# power_unit.net
KiCad netlist of a schematic drawn in Altium Designer
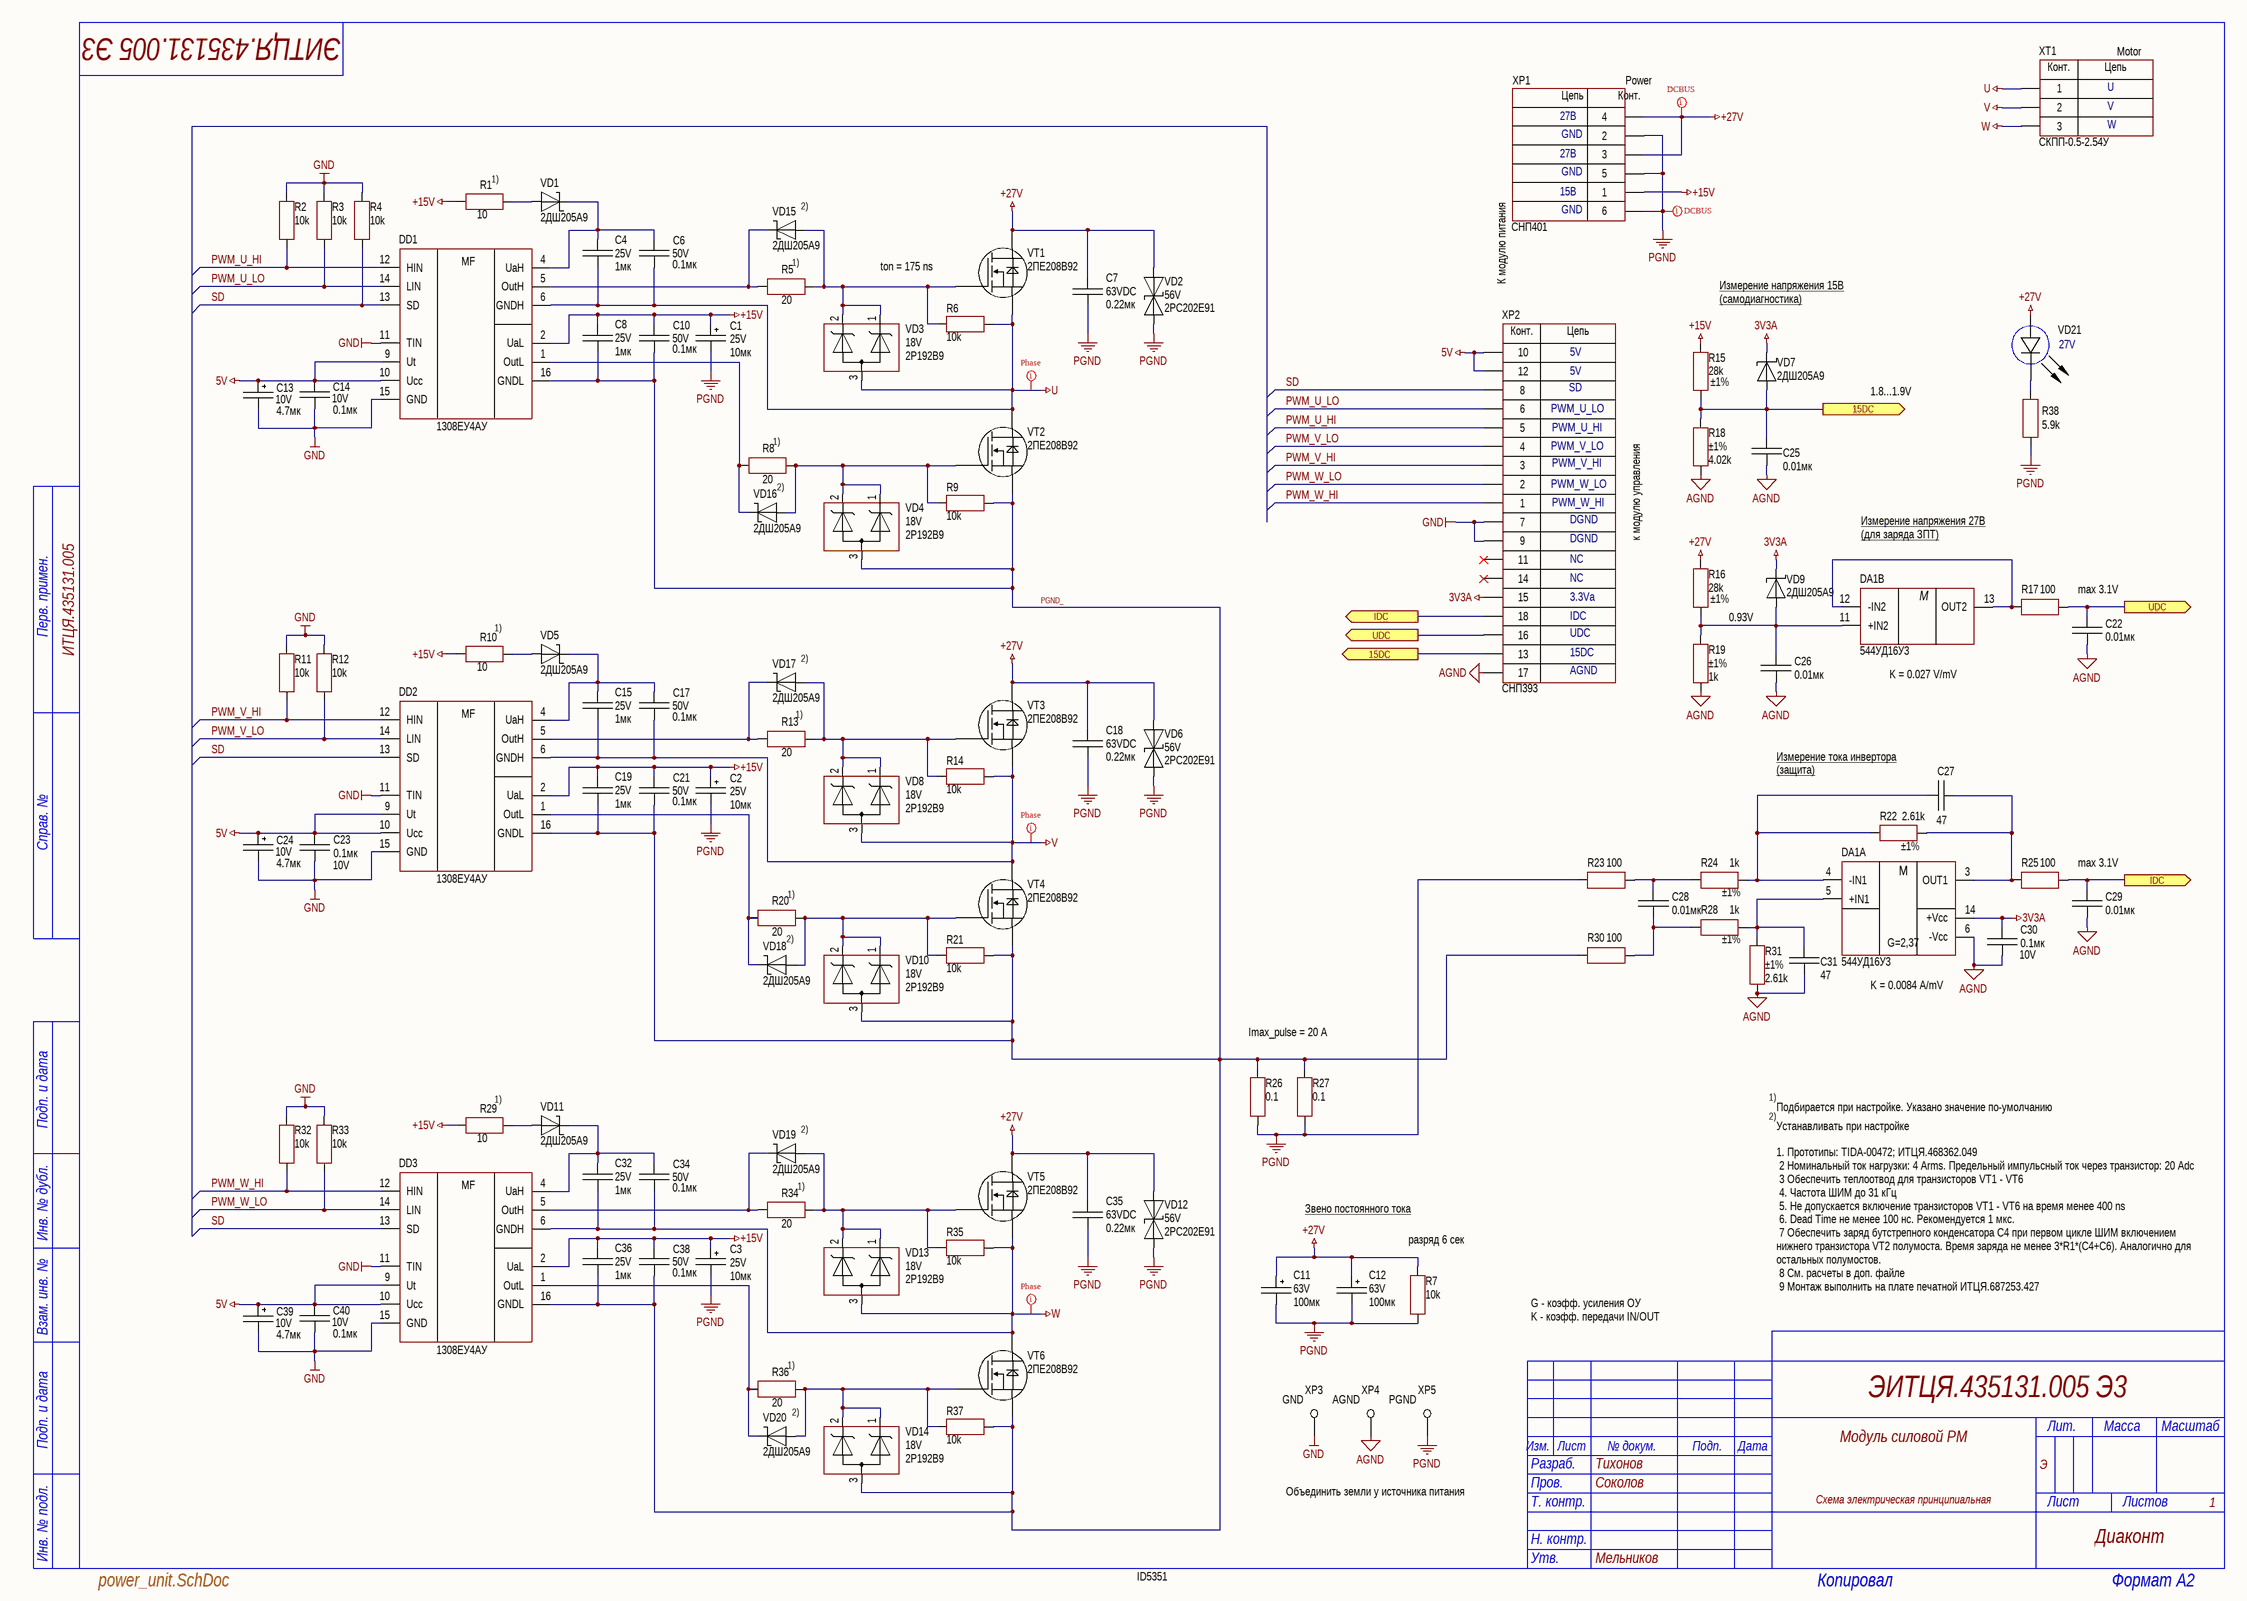
[diagram p0: power_unit.SchDoc]

(export (version "E")
  (design (tool "Eeschema 10.0.6"))
  (components
    (comp (ref "C1")
      (value "10мк")
      (footprint "StandardCase:CAP: TANTAL-C")
      (fields
        (field (name "MANUFACTURER") "Элеконд")
        (field (name "PARTNUMBER") "К53-68 \"С\"-25 В-10 мкф ±10%")
        (field (name "VALUEMANUFACTURERPARTNUMBER") "Tantalum capacitor, 10мк, 25V, ±10%, 0.8-1Ohm, case C (6032), -60...+125°C")
        (field (name "VOLTAGE") "25V")
      )
      (libsource (lib "Capacitor") (part "Tantal_C"))
    )
    (comp (ref "C2")
      (value "10мк")
      (footprint "StandardCase:CAP: TANTAL-C")
      (fields
        (field (name "MANUFACTURER") "Элеконд")
        (field (name "PARTNUMBER") "К53-68 \"С\"-25 В-10 мкф ±10%")
        (field (name "VALUEMANUFACTURERPARTNUMBER") "Tantalum capacitor, 10мк, 25V, ±10%, 0.8-1Ohm, case C (6032), -60...+125°C")
        (field (name "VOLTAGE") "25V")
      )
      (libsource (lib "Capacitor") (part "Tantal_C"))
    )
    (comp (ref "C3")
      (value "10мк")
      (footprint "StandardCase:CAP: TANTAL-C")
      (fields
        (field (name "MANUFACTURER") "Элеконд")
        (field (name "PARTNUMBER") "К53-68 \"С\"-25 В-10 мкф ±10%")
        (field (name "VALUEMANUFACTURERPARTNUMBER") "Tantalum capacitor, 10мк, 25V, ±10%, 0.8-1Ohm, case C (6032), -60...+125°C")
        (field (name "VOLTAGE") "25V")
      )
      (libsource (lib "Capacitor") (part "Tantal_C"))
    )
    (comp (ref "C4")
      (value "1мк")
      (footprint "StandardCase:CAP: 1210")
      (fields
        (field (name "MANUFACTURER") "Monolit")
        (field (name "PARTNUMBER") "К10-84в-3225М-25~В-Н20-1 мкФ-O-A ±10% ФЦТА.673516.016 ТУ")
        (field (name "VALUEMANUFACTURERPARTNUMBER") "Ceramic capacitor, 1мк, Н20 (X7R), ±10%, 25V, 1210, -55...+125°C")
        (field (name "VOLTAGE") "25V")
      )
      (libsource (lib "Capacitor") (part "Ceramic_1210"))
    )
    (comp (ref "C6")
      (value "0.1мк")
      (footprint "StandardCase:CAP: 0805P")
      (fields
        (field (name "MANUFACTURER") "Монолит")
        (field (name "PARTNUMBER") "К10-84в-2012М-50В-0,1 мкФ +80/-20%-Н90-N-A")
        (field (name "VALUEMANUFACTURERPARTNUMBER") "Ceramic capacitor, 0.1мк, Н90 (Y5V), +80 -20%, 50V, 0805 (2012), -55...+125°C")
        (field (name "VOLTAGE") "50V")
      )
      (libsource (lib "Capacitor") (part "Ceramic_0805"))
    )
    (comp (ref "C7")
      (value "0.22мк")
      (footprint "CAP: K73-17 12x10x6")
      (fields
        (field (name "MANUFACTURER") "Гириконд")
        (field (name "PARTNUMBER") "K73-17-63В-0,22мкФ±10%-В АЖЯР.673633.004 ТУ")
        (field (name "VALUEMANUFACTURERPARTNUMBER") "Film capacitor, 0.22мк, 63VDC, ±10%, , 12x10 mm, -60...+125°C")
        (field (name "VOLTAGE") "63VDC")
      )
      (libsource (lib "Capacitor") (part "Film"))
    )
    (comp (ref "C8")
      (value "1мк")
      (footprint "StandardCase:CAP: 1210")
      (fields
        (field (name "MANUFACTURER") "Monolit")
        (field (name "PARTNUMBER") "К10-84в-3225М-25~В-Н20-1 мкФ-O-A ±10% ФЦТА.673516.016 ТУ")
        (field (name "VALUEMANUFACTURERPARTNUMBER") "Ceramic capacitor, 1мк, Н20 (X7R), ±10%, 25V, 1210, -55...+125°C")
        (field (name "VOLTAGE") "25V")
      )
      (libsource (lib "Capacitor") (part "Ceramic_1210"))
    )
    (comp (ref "C10")
      (value "0.1мк")
      (footprint "StandardCase:CAP: 0805P")
      (fields
        (field (name "MANUFACTURER") "Монолит")
        (field (name "PARTNUMBER") "К10-84в-2012М-50В-0,1 мкФ +80/-20%-Н90-N-A")
        (field (name "VALUEMANUFACTURERPARTNUMBER") "Ceramic capacitor, 0.1мк, Н90 (Y5V), +80 -20%, 50V, 0805 (2012), -55...+125°C")
        (field (name "VOLTAGE") "50V")
      )
      (libsource (lib "Capacitor") (part "Ceramic_0805"))
    )
    (comp (ref "C11")
      (value "100мк")
      (footprint "StandardCase:CAP: D8C3.5H12")
      (fields
        (field (name "MANUFACTURER") "Элеконд")
        (field (name "PARTNUMBER") "K50-93-63В-100мкФ ±20% -И-В АЖЯР.673541.021 ТУ")
        (field (name "VALUEMANUFACTURERPARTNUMBER") "Aluminium capacitor, 100мк, 63V, ±20%, 0.342Ohm@100kHz, 8x11.3x3.5 mm, -60...+100°C")
        (field (name "VOLTAGE") "63V")
      )
      (libsource (lib "Capacitor") (part "Aluminium"))
    )
    (comp (ref "C12")
      (value "100мк")
      (footprint "StandardCase:CAP: D8C3.5H12")
      (fields
        (field (name "MANUFACTURER") "Элеконд")
        (field (name "PARTNUMBER") "K50-93-63В-100мкФ ±20% -И-В АЖЯР.673541.021 ТУ")
        (field (name "VALUEMANUFACTURERPARTNUMBER") "Aluminium capacitor, 100мк, 63V, ±20%, 0.342Ohm@100kHz, 8x11.3x3.5 mm, -60...+100°C")
        (field (name "VOLTAGE") "63V")
      )
      (libsource (lib "Capacitor") (part "Aluminium"))
    )
    (comp (ref "C13")
      (value "4.7мк")
      (footprint "StandardCase:CAP: TANTAL-A")
      (fields
        (field (name "MANUFACTURER") "Элеконд")
        (field (name "PARTNUMBER") "К53-68 \"А\"-10 В-4.7 мкф")
        (field (name "VALUEMANUFACTURERPARTNUMBER") "Tantalum capacitor, 4.7мк, 10V, ±10%, 2Ohm, case A (3216), -55...+125°C")
        (field (name "VOLTAGE") "10V")
      )
      (libsource (lib "Capacitor") (part "Tantal_A"))
    )
    (comp (ref "C14")
      (value "0.1мк")
      (footprint "StandardCase:CAP: 0603P")
      (fields
        (field (name "MANUFACTURER") "Гириконд")
        (field (name "PARTNUMBER") "К10-79-10В-0,1 мкФ +80-20% H90")
        (field (name "VALUEMANUFACTURERPARTNUMBER") "Ceramic capacitor, 0.1мк, H90, +80-20%, 10V, 0603, -55...+125°C")
        (field (name "VOLTAGE") "10V")
      )
      (libsource (lib "Capacitor") (part "Ceramic_0603"))
    )
    (comp (ref "C15")
      (value "1мк")
      (footprint "StandardCase:CAP: 1210")
      (fields
        (field (name "MANUFACTURER") "Monolit")
        (field (name "PARTNUMBER") "К10-84в-3225М-25~В-Н20-1 мкФ-O-A ±10% ФЦТА.673516.016 ТУ")
        (field (name "VALUEMANUFACTURERPARTNUMBER") "Ceramic capacitor, 1мк, Н20 (X7R), ±10%, 25V, 1210, -55...+125°C")
        (field (name "VOLTAGE") "25V")
      )
      (libsource (lib "Capacitor") (part "Ceramic_1210"))
    )
    (comp (ref "C17")
      (value "0.1мк")
      (footprint "StandardCase:CAP: 0805P")
      (fields
        (field (name "MANUFACTURER") "Монолит")
        (field (name "PARTNUMBER") "К10-84в-2012М-50В-0,1 мкФ +80/-20%-Н90-N-A")
        (field (name "VALUEMANUFACTURERPARTNUMBER") "Ceramic capacitor, 0.1мк, Н90 (Y5V), +80 -20%, 50V, 0805 (2012), -55...+125°C")
        (field (name "VOLTAGE") "50V")
      )
      (libsource (lib "Capacitor") (part "Ceramic_0805"))
    )
    (comp (ref "C18")
      (value "0.22мк")
      (footprint "CAP: K73-17 12x10x6")
      (fields
        (field (name "MANUFACTURER") "Гириконд")
        (field (name "PARTNUMBER") "K73-17-63В-0,22мкФ±10%-В АЖЯР.673633.004 ТУ")
        (field (name "VALUEMANUFACTURERPARTNUMBER") "Film capacitor, 0.22мк, 63VDC, ±10%, , 12x10 mm, -60...+125°C")
        (field (name "VOLTAGE") "63VDC")
      )
      (libsource (lib "Capacitor") (part "Film"))
    )
    (comp (ref "C19")
      (value "1мк")
      (footprint "StandardCase:CAP: 1210")
      (fields
        (field (name "MANUFACTURER") "Monolit")
        (field (name "PARTNUMBER") "К10-84в-3225М-25~В-Н20-1 мкФ-O-A ±10% ФЦТА.673516.016 ТУ")
        (field (name "VALUEMANUFACTURERPARTNUMBER") "Ceramic capacitor, 1мк, Н20 (X7R), ±10%, 25V, 1210, -55...+125°C")
        (field (name "VOLTAGE") "25V")
      )
      (libsource (lib "Capacitor") (part "Ceramic_1210"))
    )
    (comp (ref "C21")
      (value "0.1мк")
      (footprint "StandardCase:CAP: 0805P")
      (fields
        (field (name "MANUFACTURER") "Монолит")
        (field (name "PARTNUMBER") "К10-84в-2012М-50В-0,1 мкФ +80/-20%-Н90-N-A")
        (field (name "VALUEMANUFACTURERPARTNUMBER") "Ceramic capacitor, 0.1мк, Н90 (Y5V), +80 -20%, 50V, 0805 (2012), -55...+125°C")
        (field (name "VOLTAGE") "50V")
      )
      (libsource (lib "Capacitor") (part "Ceramic_0805"))
    )
    (comp (ref "C22")
      (value "0.01мк")
      (footprint "StandardCase:CAP: 0603P")
      (fields
        (field (name "MANUFACTURER") "Монолит")
        (field (name "PARTNUMBER") "К10-84в-1608М-50В-0.01мк ±20%-Н20-N-A")
        (field (name "VALUEMANUFACTURERPARTNUMBER") "Ceramic capacitor, 0.01мк, H20, ±20%, 50V, 0603, -55...+125°C")
      )
      (libsource (lib "Capacitor") (part "Ceramic_0603"))
    )
    (comp (ref "C23")
      (value "0.1мк")
      (footprint "StandardCase:CAP: 0603P")
      (fields
        (field (name "MANUFACTURER") "Гириконд")
        (field (name "PARTNUMBER") "К10-79-10В-0,1 мкФ +80-20% H90")
        (field (name "VALUEMANUFACTURERPARTNUMBER") "Ceramic capacitor, 0.1мк, H90, +80-20%, 10V, 0603, -55...+125°C")
        (field (name "VOLTAGE") "10V")
      )
      (libsource (lib "Capacitor") (part "Ceramic_0603"))
    )
    (comp (ref "C24")
      (value "4.7мк")
      (footprint "StandardCase:CAP: TANTAL-A")
      (fields
        (field (name "MANUFACTURER") "Элеконд")
        (field (name "PARTNUMBER") "К53-68 \"А\"-10 В-4.7 мкф")
        (field (name "VALUEMANUFACTURERPARTNUMBER") "Tantalum capacitor, 4.7мк, 10V, ±10%, 2Ohm, case A (3216), -55...+125°C")
        (field (name "VOLTAGE") "10V")
      )
      (libsource (lib "Capacitor") (part "Tantal_A"))
    )
    (comp (ref "C25")
      (value "0.01мк")
      (footprint "StandardCase:CAP: 0603P")
      (fields
        (field (name "MANUFACTURER") "Монолит")
        (field (name "PARTNUMBER") "К10-84в-1608М-50В-0.01мк ±20%-Н20-N-A")
        (field (name "VALUEMANUFACTURERPARTNUMBER") "Ceramic capacitor, 0.01мк, H20, ±20%, 50V, 0603, -55...+125°C")
      )
      (libsource (lib "Capacitor") (part "Ceramic_0603"))
    )
    (comp (ref "C26")
      (value "0.01мк")
      (footprint "StandardCase:CAP: 0603P")
      (fields
        (field (name "MANUFACTURER") "Монолит")
        (field (name "PARTNUMBER") "К10-84в-1608М-50В-0.01мк ±20%-Н20-N-A")
        (field (name "VALUEMANUFACTURERPARTNUMBER") "Ceramic capacitor, 0.01мк, H20, ±20%, 50V, 0603, -55...+125°C")
      )
      (libsource (lib "Capacitor") (part "Ceramic_0603"))
    )
    (comp (ref "C27")
      (value "47")
      (footprint "StandardCase:CAP: 0603P")
      (fields
        (field (name "MANUFACTURER") "Монолит")
        (field (name "PARTNUMBER") "К10-84в-1608М-50В-47 пФ ±10%-МП0-N-A")
        (field (name "VALUEMANUFACTURERPARTNUMBER") "Ceramic capacitor, 47, МП0, ±10%, 50V, 0603, -55...+125°C")
      )
      (libsource (lib "Capacitor") (part "Ceramic_0603"))
    )
    (comp (ref "C28")
      (value "0.01мк")
      (footprint "StandardCase:CAP: 0603P")
      (fields
        (field (name "MANUFACTURER") "Монолит")
        (field (name "PARTNUMBER") "К10-84в-1608М-50В-0.01мк ±20%-Н20-N-A")
        (field (name "VALUEMANUFACTURERPARTNUMBER") "Ceramic capacitor, 0.01мк, H20, ±20%, 50V, 0603, -55...+125°C")
      )
      (libsource (lib "Capacitor") (part "Ceramic_0603"))
    )
    (comp (ref "C29")
      (value "0.01мк")
      (footprint "StandardCase:CAP: 0603P")
      (fields
        (field (name "MANUFACTURER") "Монолит")
        (field (name "PARTNUMBER") "К10-84в-1608М-50В-0.01мк ±20%-Н20-N-A")
        (field (name "VALUEMANUFACTURERPARTNUMBER") "Ceramic capacitor, 0.01мк, H20, ±20%, 50V, 0603, -55...+125°C")
      )
      (libsource (lib "Capacitor") (part "Ceramic_0603"))
    )
    (comp (ref "C30")
      (value "0.1мк")
      (footprint "StandardCase:CAP: 0603P")
      (fields
        (field (name "MANUFACTURER") "Гириконд")
        (field (name "PARTNUMBER") "К10-79-10В-0,1 мкФ +80-20% H90")
        (field (name "VALUEMANUFACTURERPARTNUMBER") "Ceramic capacitor, 0.1мк, H90, +80-20%, 10V, 0603, -55...+125°C")
        (field (name "VOLTAGE") "10V")
      )
      (libsource (lib "Capacitor") (part "Ceramic_0603"))
    )
    (comp (ref "C31")
      (value "47")
      (footprint "StandardCase:CAP: 0603P")
      (fields
        (field (name "MANUFACTURER") "Монолит")
        (field (name "PARTNUMBER") "К10-84в-1608М-50В-47 пФ ±10%-МП0-N-A")
        (field (name "VALUEMANUFACTURERPARTNUMBER") "Ceramic capacitor, 47, МП0, ±10%, 50V, 0603, -55...+125°C")
      )
      (libsource (lib "Capacitor") (part "Ceramic_0603"))
    )
    (comp (ref "C32")
      (value "1мк")
      (footprint "StandardCase:CAP: 1210")
      (fields
        (field (name "MANUFACTURER") "Monolit")
        (field (name "PARTNUMBER") "К10-84в-3225М-25~В-Н20-1 мкФ-O-A ±10% ФЦТА.673516.016 ТУ")
        (field (name "VALUEMANUFACTURERPARTNUMBER") "Ceramic capacitor, 1мк, Н20 (X7R), ±10%, 25V, 1210, -55...+125°C")
        (field (name "VOLTAGE") "25V")
      )
      (libsource (lib "Capacitor") (part "Ceramic_1210"))
    )
    (comp (ref "C34")
      (value "0.1мк")
      (footprint "StandardCase:CAP: 0805P")
      (fields
        (field (name "MANUFACTURER") "Монолит")
        (field (name "PARTNUMBER") "К10-84в-2012М-50В-0,1 мкФ +80/-20%-Н90-N-A")
        (field (name "VALUEMANUFACTURERPARTNUMBER") "Ceramic capacitor, 0.1мк, Н90 (Y5V), +80 -20%, 50V, 0805 (2012), -55...+125°C")
        (field (name "VOLTAGE") "50V")
      )
      (libsource (lib "Capacitor") (part "Ceramic_0805"))
    )
    (comp (ref "C35")
      (value "0.22мк")
      (footprint "CAP: K73-17 12x10x6")
      (fields
        (field (name "MANUFACTURER") "Гириконд")
        (field (name "PARTNUMBER") "K73-17-63В-0,22мкФ±10%-В АЖЯР.673633.004 ТУ")
        (field (name "VALUEMANUFACTURERPARTNUMBER") "Film capacitor, 0.22мк, 63VDC, ±10%, , 12x10 mm, -60...+125°C")
        (field (name "VOLTAGE") "63VDC")
      )
      (libsource (lib "Capacitor") (part "Film"))
    )
    (comp (ref "C36")
      (value "1мк")
      (footprint "StandardCase:CAP: 1210")
      (fields
        (field (name "MANUFACTURER") "Monolit")
        (field (name "PARTNUMBER") "К10-84в-3225М-25~В-Н20-1 мкФ-O-A ±10% ФЦТА.673516.016 ТУ")
        (field (name "VALUEMANUFACTURERPARTNUMBER") "Ceramic capacitor, 1мк, Н20 (X7R), ±10%, 25V, 1210, -55...+125°C")
        (field (name "VOLTAGE") "25V")
      )
      (libsource (lib "Capacitor") (part "Ceramic_1210"))
    )
    (comp (ref "C38")
      (value "0.1мк")
      (footprint "StandardCase:CAP: 0805P")
      (fields
        (field (name "MANUFACTURER") "Монолит")
        (field (name "PARTNUMBER") "К10-84в-2012М-50В-0,1 мкФ +80/-20%-Н90-N-A")
        (field (name "VALUEMANUFACTURERPARTNUMBER") "Ceramic capacitor, 0.1мк, Н90 (Y5V), +80 -20%, 50V, 0805 (2012), -55...+125°C")
        (field (name "VOLTAGE") "50V")
      )
      (libsource (lib "Capacitor") (part "Ceramic_0805"))
    )
    (comp (ref "C39")
      (value "4.7мк")
      (footprint "StandardCase:CAP: TANTAL-A")
      (fields
        (field (name "MANUFACTURER") "Элеконд")
        (field (name "PARTNUMBER") "К53-68 \"А\"-10 В-4.7 мкф")
        (field (name "VALUEMANUFACTURERPARTNUMBER") "Tantalum capacitor, 4.7мк, 10V, ±10%, 2Ohm, case A (3216), -55...+125°C")
        (field (name "VOLTAGE") "10V")
      )
      (libsource (lib "Capacitor") (part "Tantal_A"))
    )
    (comp (ref "C40")
      (value "0.1мк")
      (footprint "StandardCase:CAP: 0603P")
      (fields
        (field (name "MANUFACTURER") "Гириконд")
        (field (name "PARTNUMBER") "К10-79-10В-0,1 мкФ +80-20% H90")
        (field (name "VALUEMANUFACTURERPARTNUMBER") "Ceramic capacitor, 0.1мк, H90, +80-20%, 10V, 0603, -55...+125°C")
        (field (name "VOLTAGE") "10V")
      )
      (libsource (lib "Capacitor") (part "Ceramic_0603"))
    )
    (comp (ref "DA1")
      (value "544УД16У3 (Н04.16-1В) АЕЯР.431130.510 ТУ_разнесенная 1")
      (footprint "16-Н04.16-1B")
      (description "Op. Amp rail-to-rail")
      (fields
        (field (name "MANUFACTURER") "НПП \"Восток\"")
        (field (name "PART_NUMBER") "544УД16У3")
        (field (name "PUBLISHER") "Sokolov")
      )
      (libsource (lib "IC. Amplifier") (part "544УД16У3 (Н04.16-1В) АЕЯР.431130.510 ТУ_разнесенная 1"))
    )
    (comp (ref "DD1")
      (value "~")
      (footprint "16-Н04.16-1B")
      (description "Gate driver")
      (fields
        (field (name "MANUFACTURER") "Кремний Эл")
        (field (name "VALUEMANUFACTURERPARTNUMBER") "Hight&Low side gate driver, , , 2A, supply 4...15V, , Н04.16-2В")
        (field (name "PARTNUMBER") "1308ЕУ4АУ")
      )
      (libsource (lib "IC. Gate driver") (part "1308ЕУ4БУ"))
    )
    (comp (ref "DD2")
      (value "~")
      (footprint "16-Н04.16-1B")
      (description "Gate driver")
      (fields
        (field (name "MANUFACTURER") "Кремний Эл")
        (field (name "VALUEMANUFACTURERPARTNUMBER") "Hight&Low side gate driver, , , 2A, supply 4...15V, , Н04.16-2В")
        (field (name "PARTNUMBER") "1308ЕУ4АУ")
      )
      (libsource (lib "IC. Gate driver") (part "1308ЕУ4БУ"))
    )
    (comp (ref "DD3")
      (value "~")
      (footprint "16-Н04.16-1B")
      (description "Gate driver")
      (fields
        (field (name "MANUFACTURER") "Кремний Эл")
        (field (name "VALUEMANUFACTURERPARTNUMBER") "Hight&Low side gate driver, , , 2A, supply 4...15V, , Н04.16-2В")
        (field (name "PARTNUMBER") "1308ЕУ4АУ")
      )
      (libsource (lib "IC. Gate driver") (part "1308ЕУ4БУ"))
    )
    (comp (ref "R1")
      (value "10")
      (footprint "StandardCase:RES: 0603P")
      (fields
        (field (name "MANUFACTURER") "ОАО Ресурс")
        (field (name "PARTNUMBER") "Р1-12-0,1ум.-10~Ом ±2%-М ШКАБ.434110.002 ТУ")
        (field (name "VALUEMANUFACTURERPARTNUMBER") "Resistor film, 10, ±5%, 0603, 0.1W, -55...+125°C")
      )
      (libsource (lib "Resistor") (part "Resistor_0603"))
    )
    (comp (ref "R2")
      (value "10k")
      (footprint "StandardCase:RES: 0603P")
      (fields
        (field (name "MANUFACTURER") "ОАО Ресурс")
        (field (name "PARTNUMBER") "Р1-12-0,1ум.-10~кОм ±5%-М ШКАБ.434110.002 ТУ")
        (field (name "VALUEMANUFACTURERPARTNUMBER") "Resistor film, 10k, ±5%, 0603, 0.1W, -55...+125°C")
      )
      (libsource (lib "") (part "Resistor_0603_1"))
    )
    (comp (ref "R3")
      (value "10k")
      (footprint "StandardCase:RES: 0603P")
      (fields
        (field (name "MANUFACTURER") "ОАО Ресурс")
        (field (name "PARTNUMBER") "Р1-12-0,1ум.-10~кОм ±5%-М ШКАБ.434110.002 ТУ")
        (field (name "VALUEMANUFACTURERPARTNUMBER") "Resistor film, 10k, ±5%, 0603, 0.1W, -55...+125°C")
      )
      (libsource (lib "") (part "Resistor_0603_1"))
    )
    (comp (ref "R4")
      (value "10k")
      (footprint "StandardCase:RES: 0603P")
      (fields
        (field (name "MANUFACTURER") "ОАО Ресурс")
        (field (name "PARTNUMBER") "Р1-12-0,1ум.-10~кОм ±5%-М ШКАБ.434110.002 ТУ")
        (field (name "VALUEMANUFACTURERPARTNUMBER") "Resistor film, 10k, ±5%, 0603, 0.1W, -55...+125°C")
      )
      (libsource (lib "") (part "Resistor_0603_1"))
    )
    (comp (ref "R5")
      (value "20")
      (footprint "StandardCase:RES: 0805P")
      (fields
        (field (name "MANUFACTURER") "ОАО Ресурс")
        (field (name "PARTNUMBER") "Р1-12-0,125-20 Ом ±1%-М ШКАБ.434110.002 ТУ")
        (field (name "VALUEMANUFACTURERPARTNUMBER") "Resistor film, 20, ±1%, 0805, 0.125W, -55...+125°C")
      )
      (libsource (lib "Resistor") (part "Resistor_0805"))
    )
    (comp (ref "R6")
      (value "10k")
      (footprint "StandardCase:RES: 0603P")
      (fields
        (field (name "MANUFACTURER") "ОАО Ресурс")
        (field (name "PARTNUMBER") "Р1-12-0,1ум.-10~кОм ±5%-М ШКАБ.434110.002 ТУ")
        (field (name "VALUEMANUFACTURERPARTNUMBER") "Resistor film, 10k, ±5%, 0603, 0.1W, -55...+125°C")
      )
      (libsource (lib "") (part "Resistor_0603_2"))
    )
    (comp (ref "R7")
      (value "10k")
      (footprint "RES: 0805P")
      (fields
        (field (name "MANUFACTURER") "ОАО Ресурс")
        (field (name "PARTNUMBER") "Р1-12-0,125-10~кОм ±1%-М ШКАБ.434110.002 ТУ")
        (field (name "VALUEMANUFACTURERPARTNUMBER") "Resistor film, 10k, ±1%, 0805, 0.125W, -55...+125°C")
      )
      (libsource (lib "") (part "Resistor_0603_1"))
    )
    (comp (ref "R8")
      (value "20")
      (footprint "StandardCase:RES: 0805P")
      (fields
        (field (name "MANUFACTURER") "ОАО Ресурс")
        (field (name "PARTNUMBER") "Р1-12-0,125-20 Ом ±1%-М ШКАБ.434110.002 ТУ")
        (field (name "VALUEMANUFACTURERPARTNUMBER") "Resistor film, 20, ±1%, 0805, 0.125W, -55...+125°C")
      )
      (libsource (lib "Resistor") (part "Resistor_0805"))
    )
    (comp (ref "R9")
      (value "10k")
      (footprint "StandardCase:RES: 0603P")
      (fields
        (field (name "MANUFACTURER") "ОАО Ресурс")
        (field (name "PARTNUMBER") "Р1-12-0,1ум.-10~кОм ±5%-М ШКАБ.434110.002 ТУ")
        (field (name "VALUEMANUFACTURERPARTNUMBER") "Resistor film, 10k, ±5%, 0603, 0.1W, -55...+125°C")
      )
      (libsource (lib "") (part "Resistor_0603_2"))
    )
    (comp (ref "R10")
      (value "10")
      (footprint "StandardCase:RES: 0603P")
      (fields
        (field (name "MANUFACTURER") "ОАО Ресурс")
        (field (name "PARTNUMBER") "Р1-12-0,1ум.-10~Ом ±2%-М ШКАБ.434110.002 ТУ")
        (field (name "VALUEMANUFACTURERPARTNUMBER") "Resistor film, 10, ±5%, 0603, 0.1W, -55...+125°C")
      )
      (libsource (lib "Resistor") (part "Resistor_0603"))
    )
    (comp (ref "R11")
      (value "10k")
      (footprint "StandardCase:RES: 0603P")
      (fields
        (field (name "MANUFACTURER") "ОАО Ресурс")
        (field (name "PARTNUMBER") "Р1-12-0,1ум.-10~кОм ±5%-М ШКАБ.434110.002 ТУ")
        (field (name "VALUEMANUFACTURERPARTNUMBER") "Resistor film, 10k, ±5%, 0603, 0.1W, -55...+125°C")
      )
      (libsource (lib "") (part "Resistor_0603_1"))
    )
    (comp (ref "R12")
      (value "10k")
      (footprint "StandardCase:RES: 0603P")
      (fields
        (field (name "MANUFACTURER") "ОАО Ресурс")
        (field (name "PARTNUMBER") "Р1-12-0,1ум.-10~кОм ±5%-М ШКАБ.434110.002 ТУ")
        (field (name "VALUEMANUFACTURERPARTNUMBER") "Resistor film, 10k, ±5%, 0603, 0.1W, -55...+125°C")
      )
      (libsource (lib "") (part "Resistor_0603_1"))
    )
    (comp (ref "R13")
      (value "20")
      (footprint "StandardCase:RES: 0805P")
      (fields
        (field (name "MANUFACTURER") "ОАО Ресурс")
        (field (name "PARTNUMBER") "Р1-12-0,125-20 Ом ±1%-М ШКАБ.434110.002 ТУ")
        (field (name "VALUEMANUFACTURERPARTNUMBER") "Resistor film, 20, ±1%, 0805, 0.125W, -55...+125°C")
      )
      (libsource (lib "Resistor") (part "Resistor_0805"))
    )
    (comp (ref "R14")
      (value "10k")
      (footprint "StandardCase:RES: 0603P")
      (fields
        (field (name "MANUFACTURER") "ОАО Ресурс")
        (field (name "PARTNUMBER") "Р1-12-0,1ум.-10~кОм ±5%-М ШКАБ.434110.002 ТУ")
        (field (name "VALUEMANUFACTURERPARTNUMBER") "Resistor film, 10k, ±5%, 0603, 0.1W, -55...+125°C")
      )
      (libsource (lib "") (part "Resistor_0603_2"))
    )
    (comp (ref "R15")
      (value "28k")
      (footprint "StandardCase:RES: 0603P")
      (fields
        (field (name "MANUFACTURER") "ОАО Ресурс")
        (field (name "PARTNUMBER") "Р1-12-0,1ум.-28~кОм ±5%-М ШКАБ.434110.002 ТУ")
        (field (name "VALUEMANUFACTURERPARTNUMBER") "Resistor film, 28k, ±1%, 0603, 0.1W, -55...+125°C")
        (field (name "TOLERANCE") "±1%")
      )
      (libsource (lib "") (part "Resistor_0603_1"))
    )
    (comp (ref "R16")
      (value "28k")
      (footprint "StandardCase:RES: 0603P")
      (fields
        (field (name "MANUFACTURER") "ОАО Ресурс")
        (field (name "PARTNUMBER") "Р1-12-0,1ум.-28~кОм ±5%-М ШКАБ.434110.002 ТУ")
        (field (name "VALUEMANUFACTURERPARTNUMBER") "Resistor film, 28k, ±1%, 0603, 0.1W, -55...+125°C")
        (field (name "TOLERANCE") "±1%")
      )
      (libsource (lib "") (part "Resistor_0603_1"))
    )
    (comp (ref "R17")
      (value "100")
      (footprint "StandardCase:RES: 0603P")
      (fields
        (field (name "MANUFACTURER") "ОАО Ресурс")
        (field (name "PARTNUMBER") "Р1-12-0,1ум.-100~Ом ±5%-М ШКАБ.434110.002 ТУ")
        (field (name "VALUEMANUFACTURERPARTNUMBER") "Resistor film, 100, ±5%, 0603, 0.1W, -55...+125°C")
      )
      (libsource (lib "Resistor") (part "Resistor_0603"))
    )
    (comp (ref "R18")
      (value "4.02k")
      (footprint "StandardCase:RES: 0603P")
      (fields
        (field (name "MANUFACTURER") "ОАО Ресурс")
        (field (name "PARTNUMBER") "Р1-12-0,1ум.-4.02~кОм±1%-М ШКАБ.434110.002 ТУ")
        (field (name "VALUEMANUFACTURERPARTNUMBER") "Resistor film, 4.02k, ±1%, 0603, 0.1W, -55...+125°C")
        (field (name "TOLERANCE") "±1%")
      )
      (libsource (lib "") (part "Resistor_0603_1"))
    )
    (comp (ref "R19")
      (value "1k")
      (footprint "StandardCase:RES: 0603P")
      (fields
        (field (name "MANUFACTURER") "ОАО Ресурс")
        (field (name "PARTNUMBER") "Р1-12-0,1ум.-1~кОм ±1%-М ШКАБ.434110.002 ТУ")
        (field (name "VALUEMANUFACTURERPARTNUMBER") "Resistor film, 1k, ±1%, 0603, 0.1W, -55...+125°C")
        (field (name "TOLERANCE") "±1%")
      )
      (libsource (lib "") (part "Resistor_0603_1"))
    )
    (comp (ref "R20")
      (value "20")
      (footprint "StandardCase:RES: 0805P")
      (fields
        (field (name "MANUFACTURER") "ОАО Ресурс")
        (field (name "PARTNUMBER") "Р1-12-0,125-20 Ом ±1%-М ШКАБ.434110.002 ТУ")
        (field (name "VALUEMANUFACTURERPARTNUMBER") "Resistor film, 20, ±1%, 0805, 0.125W, -55...+125°C")
      )
      (libsource (lib "Resistor") (part "Resistor_0805"))
    )
    (comp (ref "R21")
      (value "10k")
      (footprint "StandardCase:RES: 0603P")
      (fields
        (field (name "MANUFACTURER") "ОАО Ресурс")
        (field (name "PARTNUMBER") "Р1-12-0,1ум.-10~кОм ±5%-М ШКАБ.434110.002 ТУ")
        (field (name "VALUEMANUFACTURERPARTNUMBER") "Resistor film, 10k, ±5%, 0603, 0.1W, -55...+125°C")
      )
      (libsource (lib "") (part "Resistor_0603_2"))
    )
    (comp (ref "R22")
      (value "2.61k")
      (footprint "StandardCase:RES: 0603P")
      (fields
        (field (name "MANUFACTURER") "ОАО Ресурс")
        (field (name "PARTNUMBER") "Р1-12-0,1ум.-2.61~кОм±1%-М ШКАБ.434110.002 ТУ")
        (field (name "VALUEMANUFACTURERPARTNUMBER") "Resistor film, 2.61k, ±1%, 0603, 0.1W, -55...+125°C")
        (field (name "TOLERANCE") "±1%")
      )
      (libsource (lib "Resistor") (part "Resistor_0603"))
    )
    (comp (ref "R23")
      (value "100")
      (footprint "StandardCase:RES: 0603P")
      (fields
        (field (name "MANUFACTURER") "ОАО Ресурс")
        (field (name "PARTNUMBER") "Р1-12-0,1ум.-100~Ом ±5%-М ШКАБ.434110.002 ТУ")
        (field (name "VALUEMANUFACTURERPARTNUMBER") "Resistor film, 100, ±5%, 0603, 0.1W, -55...+125°C")
      )
      (libsource (lib "Resistor") (part "Resistor_0603"))
    )
    (comp (ref "R24")
      (value "1k")
      (footprint "StandardCase:RES: 0603P")
      (fields
        (field (name "MANUFACTURER") "ОАО Ресурс")
        (field (name "PARTNUMBER") "Р1-12-0,1ум.-1~кОм ±1%-М ШКАБ.434110.002 ТУ")
        (field (name "VALUEMANUFACTURERPARTNUMBER") "Resistor film, 1k, ±1%, 0603, 0.1W, -55...+125°C")
        (field (name "TOLERANCE") "±1%")
      )
      (libsource (lib "Resistor") (part "Resistor_0603"))
    )
    (comp (ref "R25")
      (value "100")
      (footprint "StandardCase:RES: 0603P")
      (fields
        (field (name "MANUFACTURER") "ОАО Ресурс")
        (field (name "PARTNUMBER") "Р1-12-0,1ум.-100~Ом ±5%-М ШКАБ.434110.002 ТУ")
        (field (name "VALUEMANUFACTURERPARTNUMBER") "Resistor film, 100, ±5%, 0603, 0.1W, -55...+125°C")
      )
      (libsource (lib "Resistor") (part "Resistor_0603"))
    )
    (comp (ref "R26")
      (value "0.1")
      (footprint "StandardCase:RES: 2512")
      (fields
        (field (name "MANUFACTURER") "Эркон")
        (field (name "PARTNUMBER") "Р2-105-0,75-0,1 Ом±1% А РМУ.434150.001 ТУ")
        (field (name "VALUEMANUFACTURERPARTNUMBER") "Resistor film, 0.1, ±1%, 2512, 0.75W, -55...+125°C")
      )
      (libsource (lib "Resistor") (part "Resistor_2512"))
    )
    (comp (ref "R27")
      (value "0.1")
      (footprint "StandardCase:RES: 2512")
      (fields
        (field (name "MANUFACTURER") "Эркон")
        (field (name "PARTNUMBER") "Р2-105-0,75-0,1 Ом±1% А РМУ.434150.001 ТУ")
        (field (name "VALUEMANUFACTURERPARTNUMBER") "Resistor film, 0.1, ±1%, 2512, 0.75W, -55...+125°C")
      )
      (libsource (lib "Resistor") (part "Resistor_2512"))
    )
    (comp (ref "R28")
      (value "1k")
      (footprint "StandardCase:RES: 0603P")
      (fields
        (field (name "MANUFACTURER") "ОАО Ресурс")
        (field (name "PARTNUMBER") "Р1-12-0,1ум.-1~кОм ±1%-М ШКАБ.434110.002 ТУ")
        (field (name "VALUEMANUFACTURERPARTNUMBER") "Resistor film, 1k, ±1%, 0603, 0.1W, -55...+125°C")
        (field (name "TOLERANCE") "±1%")
      )
      (libsource (lib "Resistor") (part "Resistor_0603"))
    )
    (comp (ref "R29")
      (value "10")
      (footprint "StandardCase:RES: 0603P")
      (fields
        (field (name "MANUFACTURER") "ОАО Ресурс")
        (field (name "PARTNUMBER") "Р1-12-0,1ум.-10~Ом ±2%-М ШКАБ.434110.002 ТУ")
        (field (name "VALUEMANUFACTURERPARTNUMBER") "Resistor film, 10, ±5%, 0603, 0.1W, -55...+125°C")
      )
      (libsource (lib "Resistor") (part "Resistor_0603"))
    )
    (comp (ref "R30")
      (value "100")
      (footprint "StandardCase:RES: 0603P")
      (fields
        (field (name "MANUFACTURER") "ОАО Ресурс")
        (field (name "PARTNUMBER") "Р1-12-0,1ум.-100~Ом ±5%-М ШКАБ.434110.002 ТУ")
        (field (name "VALUEMANUFACTURERPARTNUMBER") "Resistor film, 100, ±5%, 0603, 0.1W, -55...+125°C")
      )
      (libsource (lib "Resistor") (part "Resistor_0603"))
    )
    (comp (ref "R31")
      (value "2.61k")
      (footprint "StandardCase:RES: 0603P")
      (fields
        (field (name "MANUFACTURER") "ОАО Ресурс")
        (field (name "PARTNUMBER") "Р1-12-0,1ум.-2.61~кОм±1%-М ШКАБ.434110.002 ТУ")
        (field (name "VALUEMANUFACTURERPARTNUMBER") "Resistor film, 2.61k, ±1%, 0603, 0.1W, -55...+125°C")
        (field (name "TOLERANCE") "±1%")
      )
      (libsource (lib "") (part "Resistor_0603_1"))
    )
    (comp (ref "R32")
      (value "10k")
      (footprint "StandardCase:RES: 0603P")
      (fields
        (field (name "MANUFACTURER") "ОАО Ресурс")
        (field (name "PARTNUMBER") "Р1-12-0,1ум.-10~кОм ±5%-М ШКАБ.434110.002 ТУ")
        (field (name "VALUEMANUFACTURERPARTNUMBER") "Resistor film, 10k, ±5%, 0603, 0.1W, -55...+125°C")
      )
      (libsource (lib "") (part "Resistor_0603_1"))
    )
    (comp (ref "R33")
      (value "10k")
      (footprint "StandardCase:RES: 0603P")
      (fields
        (field (name "MANUFACTURER") "ОАО Ресурс")
        (field (name "PARTNUMBER") "Р1-12-0,1ум.-10~кОм ±5%-М ШКАБ.434110.002 ТУ")
        (field (name "VALUEMANUFACTURERPARTNUMBER") "Resistor film, 10k, ±5%, 0603, 0.1W, -55...+125°C")
      )
      (libsource (lib "") (part "Resistor_0603_1"))
    )
    (comp (ref "R34")
      (value "20")
      (footprint "StandardCase:RES: 0805P")
      (fields
        (field (name "MANUFACTURER") "ОАО Ресурс")
        (field (name "PARTNUMBER") "Р1-12-0,125-20 Ом ±1%-М ШКАБ.434110.002 ТУ")
        (field (name "VALUEMANUFACTURERPARTNUMBER") "Resistor film, 20, ±1%, 0805, 0.125W, -55...+125°C")
      )
      (libsource (lib "Resistor") (part "Resistor_0805"))
    )
    (comp (ref "R35")
      (value "10k")
      (footprint "StandardCase:RES: 0603P")
      (fields
        (field (name "MANUFACTURER") "ОАО Ресурс")
        (field (name "PARTNUMBER") "Р1-12-0,1ум.-10~кОм ±5%-М ШКАБ.434110.002 ТУ")
        (field (name "VALUEMANUFACTURERPARTNUMBER") "Resistor film, 10k, ±5%, 0603, 0.1W, -55...+125°C")
      )
      (libsource (lib "") (part "Resistor_0603_2"))
    )
    (comp (ref "R36")
      (value "20")
      (footprint "StandardCase:RES: 0805P")
      (fields
        (field (name "MANUFACTURER") "ОАО Ресурс")
        (field (name "PARTNUMBER") "Р1-12-0,125-20 Ом ±1%-М ШКАБ.434110.002 ТУ")
        (field (name "VALUEMANUFACTURERPARTNUMBER") "Resistor film, 20, ±1%, 0805, 0.125W, -55...+125°C")
      )
      (libsource (lib "Resistor") (part "Resistor_0805"))
    )
    (comp (ref "R37")
      (value "10k")
      (footprint "StandardCase:RES: 0603P")
      (fields
        (field (name "MANUFACTURER") "ОАО Ресурс")
        (field (name "PARTNUMBER") "Р1-12-0,1ум.-10~кОм ±5%-М ШКАБ.434110.002 ТУ")
        (field (name "VALUEMANUFACTURERPARTNUMBER") "Resistor film, 10k, ±5%, 0603, 0.1W, -55...+125°C")
      )
      (libsource (lib "") (part "Resistor_0603_2"))
    )
    (comp (ref "R38")
      (value "5.9k")
      (footprint "RES: 0805P")
      (fields
        (field (name "MANUFACTURER") "ОАО Ресурс")
        (field (name "PARTNUMBER") "Р1-12-0,1-5.9~кОм ±5%-М ШКАБ.434110.002 ТУ")
        (field (name "VALUEMANUFACTURERPARTNUMBER") "Resistor film, 5.9k, ±5%, 0805, 0.1W, -55...+125°C")
      )
      (libsource (lib "Resistor") (part "Resistor_0603"))
    )
    (comp (ref "VD1")
      (value "~")
      (footprint "SOT23")
      (fields
        (field (name "MANUFACTURER") "ВЗПП Воронеж")
        (field (name "VALUEMANUFACTURERPARTNUMBER") "shottki diode, 80V, 500mA; max 5 A@1ms, 0.8V, <22ns, SOT-23, -55...+150°C")
        (field (name "VOLTAGE") "80V")
        (field (name "PARTNUMBER") "2ДШ205А9")
      )
      (libsource (lib "Power_unit-RM") (part "2ДШ205А9_SOT-23"))
    )
    (comp (ref "VD2")
      (value "~")
      (footprint "StandardCase:DIODE: SMB")
      (fields
        (field (name "MANUFACTURER") "ВЗПП")
        (field (name "VALUEMANUFACTURERPARTNUMBER") "Zener diode, 56V, 8A, 0.9V, , SMB, -55...+150°C")
        (field (name "VOLTAGE") "56V")
        (field (name "PARTNUMBER") "2РС202Е91")
      )
      (libsource (lib "Diode") (part "TVS_single"))
    )
    (comp (ref "VD3")
      (value "~")
      (footprint "StandardCase:SOT23")
      (fields
        (field (name "MANUFACTURER") "КРИП")
        (field (name "VALUEMANUFACTURERPARTNUMBER") "TVS diode, 18V, 1A, , , SOT-23, -55...+150°C")
        (field (name "VOLTAGE") "18V")
        (field (name "PARTNUMBER") "2Р192В9")
      )
      (libsource (lib "Diode") (part "TVS_array_var2"))
    )
    (comp (ref "VD4")
      (value "~")
      (footprint "StandardCase:SOT23")
      (fields
        (field (name "MANUFACTURER") "КРИП")
        (field (name "VALUEMANUFACTURERPARTNUMBER") "TVS diode, 18V, 1A, , , SOT-23, -55...+150°C")
        (field (name "VOLTAGE") "18V")
        (field (name "PARTNUMBER") "2Р192В9")
      )
      (libsource (lib "Diode") (part "TVS_array_var2"))
    )
    (comp (ref "VD5")
      (value "~")
      (footprint "SOT23")
      (fields
        (field (name "MANUFACTURER") "ВЗПП Воронеж")
        (field (name "VALUEMANUFACTURERPARTNUMBER") "shottki diode, 80V, 500mA; max 5 A@1ms, 0.8V, <22ns, SOT-23, -55...+150°C")
        (field (name "VOLTAGE") "80V")
        (field (name "PARTNUMBER") "2ДШ205А9")
      )
      (libsource (lib "Power_unit-RM") (part "2ДШ205А9_SOT-23"))
    )
    (comp (ref "VD6")
      (value "~")
      (footprint "StandardCase:DIODE: SMB")
      (fields
        (field (name "MANUFACTURER") "ВЗПП")
        (field (name "VALUEMANUFACTURERPARTNUMBER") "Zener diode, 56V, 8A, 0.9V, , SMB, -55...+150°C")
        (field (name "VOLTAGE") "56V")
        (field (name "PARTNUMBER") "2РС202Е91")
      )
      (libsource (lib "Diode") (part "TVS_single"))
    )
    (comp (ref "VD7")
      (value "~")
      (footprint "SOT23")
      (fields
        (field (name "MANUFACTURER") "ВЗПП Воронеж")
        (field (name "VALUEMANUFACTURERPARTNUMBER") "shottki diode, 80V, 500mA; max 5 A@1ms, 0.8V, <22ns, SOT-23, -55...+150°C")
        (field (name "VOLTAGE") "80V")
        (field (name "PARTNUMBER") "2ДШ205А9")
      )
      (libsource (lib "Power_unit-RM") (part "2ДШ205А9_SOT-23"))
    )
    (comp (ref "VD8")
      (value "~")
      (footprint "StandardCase:SOT23")
      (fields
        (field (name "MANUFACTURER") "КРИП")
        (field (name "VALUEMANUFACTURERPARTNUMBER") "TVS diode, 18V, 1A, , , SOT-23, -55...+150°C")
        (field (name "VOLTAGE") "18V")
        (field (name "PARTNUMBER") "2Р192В9")
      )
      (libsource (lib "Diode") (part "TVS_array_var2"))
    )
    (comp (ref "VD9")
      (value "~")
      (footprint "SOT23")
      (fields
        (field (name "MANUFACTURER") "ВЗПП Воронеж")
        (field (name "VALUEMANUFACTURERPARTNUMBER") "shottki diode, 80V, 500mA; max 5 A@1ms, 0.8V, <22ns, SOT-23, -55...+150°C")
        (field (name "VOLTAGE") "80V")
        (field (name "PARTNUMBER") "2ДШ205А9")
      )
      (libsource (lib "Power_unit-RM") (part "2ДШ205А9_SOT-23"))
    )
    (comp (ref "VD10")
      (value "~")
      (footprint "StandardCase:SOT23")
      (fields
        (field (name "MANUFACTURER") "КРИП")
        (field (name "VALUEMANUFACTURERPARTNUMBER") "TVS diode, 18V, 1A, , , SOT-23, -55...+150°C")
        (field (name "VOLTAGE") "18V")
        (field (name "PARTNUMBER") "2Р192В9")
      )
      (libsource (lib "Diode") (part "TVS_array_var2"))
    )
    (comp (ref "VD11")
      (value "~")
      (footprint "SOT23")
      (fields
        (field (name "MANUFACTURER") "ВЗПП Воронеж")
        (field (name "VALUEMANUFACTURERPARTNUMBER") "shottki diode, 80V, 500mA; max 5 A@1ms, 0.8V, <22ns, SOT-23, -55...+150°C")
        (field (name "VOLTAGE") "80V")
        (field (name "PARTNUMBER") "2ДШ205А9")
      )
      (libsource (lib "Power_unit-RM") (part "2ДШ205А9_SOT-23"))
    )
    (comp (ref "VD12")
      (value "~")
      (footprint "StandardCase:DIODE: SMB")
      (fields
        (field (name "MANUFACTURER") "ВЗПП")
        (field (name "VALUEMANUFACTURERPARTNUMBER") "Zener diode, 56V, 8A, 0.9V, , SMB, -55...+150°C")
        (field (name "VOLTAGE") "56V")
        (field (name "PARTNUMBER") "2РС202Е91")
      )
      (libsource (lib "Diode") (part "TVS_single"))
    )
    (comp (ref "VD13")
      (value "~")
      (footprint "StandardCase:SOT23")
      (fields
        (field (name "MANUFACTURER") "КРИП")
        (field (name "VALUEMANUFACTURERPARTNUMBER") "TVS diode, 18V, 1A, , , SOT-23, -55...+150°C")
        (field (name "VOLTAGE") "18V")
        (field (name "PARTNUMBER") "2Р192В9")
      )
      (libsource (lib "Diode") (part "TVS_array_var2"))
    )
    (comp (ref "VD14")
      (value "~")
      (footprint "StandardCase:SOT23")
      (fields
        (field (name "MANUFACTURER") "КРИП")
        (field (name "VALUEMANUFACTURERPARTNUMBER") "TVS diode, 18V, 1A, , , SOT-23, -55...+150°C")
        (field (name "VOLTAGE") "18V")
        (field (name "PARTNUMBER") "2Р192В9")
      )
      (libsource (lib "Diode") (part "TVS_array_var2"))
    )
    (comp (ref "VD15")
      (value "~")
      (footprint "SOT23")
      (fields
        (field (name "MANUFACTURER") "ВЗПП Воронеж")
        (field (name "VALUEMANUFACTURERPARTNUMBER") "shottki diode, 80V, 500mA; max 5 A@1ms, 0.8V, <22ns, SOT-23, -55...+150°C")
        (field (name "VOLTAGE") "80V")
        (field (name "PARTNUMBER") "2ДШ205А9")
      )
      (libsource (lib "Power_unit-RM") (part "2ДШ205А9_SOT-23"))
    )
    (comp (ref "VD16")
      (value "~")
      (footprint "SOT23")
      (fields
        (field (name "MANUFACTURER") "ВЗПП Воронеж")
        (field (name "VALUEMANUFACTURERPARTNUMBER") "shottki diode, 80V, 500mA; max 5 A@1ms, 0.8V, <22ns, SOT-23, -55...+150°C")
        (field (name "VOLTAGE") "80V")
        (field (name "PARTNUMBER") "2ДШ205А9")
      )
      (libsource (lib "Power_unit-RM") (part "2ДШ205А9_SOT-23"))
    )
    (comp (ref "VD17")
      (value "~")
      (footprint "SOT23")
      (fields
        (field (name "MANUFACTURER") "ВЗПП Воронеж")
        (field (name "VALUEMANUFACTURERPARTNUMBER") "shottki diode, 80V, 500mA; max 5 A@1ms, 0.8V, <22ns, SOT-23, -55...+150°C")
        (field (name "VOLTAGE") "80V")
        (field (name "PARTNUMBER") "2ДШ205А9")
      )
      (libsource (lib "Power_unit-RM") (part "2ДШ205А9_SOT-23"))
    )
    (comp (ref "VD18")
      (value "~")
      (footprint "SOT23")
      (fields
        (field (name "MANUFACTURER") "ВЗПП Воронеж")
        (field (name "VALUEMANUFACTURERPARTNUMBER") "shottki diode, 80V, 500mA; max 5 A@1ms, 0.8V, <22ns, SOT-23, -55...+150°C")
        (field (name "VOLTAGE") "80V")
        (field (name "PARTNUMBER") "2ДШ205А9")
      )
      (libsource (lib "Power_unit-RM") (part "2ДШ205А9_SOT-23"))
    )
    (comp (ref "VD19")
      (value "~")
      (footprint "SOT23")
      (fields
        (field (name "MANUFACTURER") "ВЗПП Воронеж")
        (field (name "VALUEMANUFACTURERPARTNUMBER") "shottki diode, 80V, 500mA; max 5 A@1ms, 0.8V, <22ns, SOT-23, -55...+150°C")
        (field (name "VOLTAGE") "80V")
        (field (name "PARTNUMBER") "2ДШ205А9")
      )
      (libsource (lib "Power_unit-RM") (part "2ДШ205А9_SOT-23"))
    )
    (comp (ref "VD20")
      (value "~")
      (footprint "SOT23")
      (fields
        (field (name "MANUFACTURER") "ВЗПП Воронеж")
        (field (name "VALUEMANUFACTURERPARTNUMBER") "shottki diode, 80V, 500mA; max 5 A@1ms, 0.8V, <22ns, SOT-23, -55...+150°C")
        (field (name "VOLTAGE") "80V")
        (field (name "PARTNUMBER") "2ДШ205А9")
      )
      (libsource (lib "Power_unit-RM") (part "2ДШ205А9_SOT-23"))
    )
    (comp (ref "VD21")
      (value "~")
      (footprint "StandardCase:LED: 0603G")
      (fields
        (field (name "MANUFACTURER") "Протон")
        (field (name "VALUEMANUFACTURERPARTNUMBER") "LED, 20mA max, 1.9V@4mA, 1608, -55...+150°C")
        (field (name "PARTNUMBER") "ИПД169А9-Л")
        (field (name "COMMENTTEXT") "27V")
      )
      (libsource (lib "Diode") (part "LED_single"))
    )
    (comp (ref "VT1")
      (value "~")
      (footprint "DPAK")
      (description "Ангстрем (ВП)")
      (fields (field (name "MANUFACTURER") "Ангстрем") (field (name "PARTNUMBER") "2ПЕ208В92"))
      (libsource (lib "Power_unit-RM") (part "2ПЕ208В92_N_DPAK"))
    )
    (comp (ref "VT2")
      (value "~")
      (footprint "DPAK")
      (description "Ангстрем (ВП)")
      (fields (field (name "MANUFACTURER") "Ангстрем") (field (name "PARTNUMBER") "2ПЕ208В92"))
      (libsource (lib "Power_unit-RM") (part "2ПЕ208В92_N_DPAK"))
    )
    (comp (ref "VT3")
      (value "~")
      (footprint "DPAK")
      (description "Ангстрем (ВП)")
      (fields (field (name "MANUFACTURER") "Ангстрем") (field (name "PARTNUMBER") "2ПЕ208В92"))
      (libsource (lib "Power_unit-RM") (part "2ПЕ208В92_N_DPAK"))
    )
    (comp (ref "VT4")
      (value "~")
      (footprint "DPAK")
      (description "Ангстрем (ВП)")
      (fields (field (name "MANUFACTURER") "Ангстрем") (field (name "PARTNUMBER") "2ПЕ208В92"))
      (libsource (lib "Power_unit-RM") (part "2ПЕ208В92_N_DPAK"))
    )
    (comp (ref "VT5")
      (value "~")
      (footprint "DPAK")
      (description "Ангстрем (ВП)")
      (fields (field (name "MANUFACTURER") "Ангстрем") (field (name "PARTNUMBER") "2ПЕ208В92"))
      (libsource (lib "Power_unit-RM") (part "2ПЕ208В92_N_DPAK"))
    )
    (comp (ref "VT6")
      (value "~")
      (footprint "DPAK")
      (description "Ангстрем (ВП)")
      (fields (field (name "MANUFACTURER") "Ангстрем") (field (name "PARTNUMBER") "2ПЕ208В92"))
      (libsource (lib "Power_unit-RM") (part "2ПЕ208В92_N_DPAK"))
    )
    (comp (ref "XP1")
      (value "Power")
      (footprint "CON: M80-5000605")
      (description "вилка на плату")
      (fields
        (field (name "MANUFACTURER") "Электродеталь")
        (field (name "VALUEMANUFACTURERPARTNUMBER") "Вилка, 6pin, 2mm, 120VAC, 1.5A")
        (field (name "COMMENTTEXT") "СНП401")
      )
      (libsource (lib "Connector") (part "M80-5000605 Harwin"))
    )
    (comp (ref "XP2")
      (value "~")
      (footprint "CON: PLD-18R")
      (fields
        (field (name "MANUFACTURER") "Электродеталь")
        (field (name "VALUEMANUFACTURERPARTNUMBER") "Connector, 18pin, 2.54mm, 500VAC, 3A")
        (field (name "PARTNUMBER") "СНП393-18ВП31-2-01-5 РЮМК.430420.035 ТУ")
        (field (name "COMMENTTEXT") "СНП393")
      )
      (libsource (lib "Connector") (part "PLD-18"))
    )
    (comp (ref "XP3")
      (value "AGND")
      (footprint "CON: PLS2-1")
      (description "Test probe")
      (fields
        (field (name "PARTNUMBER") "СНП377-1ВП21-1")
        (field (name "MANUFACTURER") "Электродеталь")
        (field (name "PUBLISHER") "TEN")
      )
      (libsource (lib "Connector") (part "PLS2-1"))
    )
    (comp (ref "XP4")
      (value "AGND")
      (footprint "CON: PLS2-1")
      (description "Test probe")
      (fields
        (field (name "PARTNUMBER") "СНП377-1ВП21-1")
        (field (name "MANUFACTURER") "Электродеталь")
        (field (name "PUBLISHER") "TEN")
      )
      (libsource (lib "Connector") (part "PLS2-1"))
    )
    (comp (ref "XP5")
      (value "AGND")
      (footprint "CON: PLS2-1")
      (description "Test probe")
      (fields
        (field (name "PARTNUMBER") "СНП377-1ВП21-1")
        (field (name "MANUFACTURER") "Электродеталь")
        (field (name "PUBLISHER") "TEN")
      )
      (libsource (lib "Connector") (part "PLS2-1"))
    )
    (comp (ref "XT1")
      (value "~")
      (footprint "CustomCase:CON: 233-403 WAGO")
      (fields
        (field (name "MANUFACTURER") "Завод Атлант")
        (field (name "VALUEMANUFACTURERPARTNUMBER") "Terminal connector, 3pin, 3.5mm, 300VAC, 6A")
        (field (name "PARTNUMBER") "СКПП-0.5-2.54У-3x2-2 СЦНК.434410.044 ТУ")
        (field (name "COMMENTTEXT") "СКПП-0.5-2.54У")
      )
      (libsource (lib "Connector") (part "Connector_terminal_3pin"))
    )
  )
  (nets
    (net (code "1") (name "+15V") (class "Default")
      (node (ref "C1") (pin "1") (pinfunction "1_1") (pintype "power_in"))
      (node (ref "C10") (pin "2") (pinfunction "2_2") (pintype "power_in"))
      (node (ref "C19") (pin "2") (pinfunction "2_2") (pintype "power_in"))
      (node (ref "C2") (pin "1") (pinfunction "1_1") (pintype "power_in"))
      (node (ref "C21") (pin "2") (pinfunction "2_2") (pintype "power_in"))
      (node (ref "C3") (pin "1") (pinfunction "1_1") (pintype "power_in"))
      (node (ref "C36") (pin "2") (pinfunction "2_2") (pintype "power_in"))
      (node (ref "C38") (pin "2") (pinfunction "2_2") (pintype "power_in"))
      (node (ref "C8") (pin "2") (pinfunction "2_2") (pintype "power_in"))
      (node (ref "DD1") (pin "2") (pinfunction "UaL_2") (pintype "passive"))
      (node (ref "DD2") (pin "2") (pinfunction "UaL_2") (pintype "passive"))
      (node (ref "DD3") (pin "2") (pinfunction "UaL_2") (pintype "passive"))
      (node (ref "R1") (pin "1") (pinfunction "1_1") (pintype "passive"))
      (node (ref "R10") (pin "1") (pinfunction "1_1") (pintype "passive"))
      (node (ref "R15") (pin "2") (pinfunction "2_2") (pintype "passive"))
      (node (ref "R29") (pin "1") (pinfunction "1_1") (pintype "passive"))
      (node (ref "XP1") (pin "1") (pinfunction "1_1") (pintype "passive"))
    )
    (net (code "2") (name "+27V") (class "Default")
      (node (ref "C11") (pin "1") (pinfunction "1_1") (pintype "power_in"))
      (node (ref "C12") (pin "1") (pinfunction "1_1") (pintype "power_in"))
      (node (ref "C18") (pin "1") (pinfunction "1_1") (pintype "power_in"))
      (node (ref "C35") (pin "1") (pinfunction "1_1") (pintype "power_in"))
      (node (ref "C7") (pin "1") (pinfunction "1_1") (pintype "power_in"))
      (node (ref "R16") (pin "2") (pinfunction "2_2") (pintype "passive"))
      (node (ref "R7") (pin "2") (pinfunction "2_2") (pintype "passive"))
      (node (ref "VD12") (pin "2") (pinfunction "C_2") (pintype "passive"))
      (node (ref "VD2") (pin "2") (pinfunction "C_2") (pintype "passive"))
      (node (ref "VD21") (pin "1") (pinfunction "A_1") (pintype "passive"))
      (node (ref "VD6") (pin "2") (pinfunction "C_2") (pintype "passive"))
      (node (ref "VT1") (pin "3") (pinfunction "D_3") (pintype "passive"))
      (node (ref "VT3") (pin "3") (pinfunction "D_3") (pintype "passive"))
      (node (ref "VT5") (pin "3") (pinfunction "D_3") (pintype "passive"))
      (node (ref "XP1") (pin "3") (pinfunction "3_3") (pintype "passive"))
      (node (ref "XP1") (pin "4") (pinfunction "4_4") (pintype "passive"))
    )
    (net (code "3") (name "/15DC") (class "Default")
      (node (ref "C25") (pin "1") (pinfunction "1_1") (pintype "power_in"))
      (node (ref "R15") (pin "1") (pinfunction "1_1") (pintype "passive"))
      (node (ref "R18") (pin "2") (pinfunction "2_2") (pintype "passive"))
      (node (ref "VD7") (pin "1") (pinfunction "A_1") (pintype "passive"))
      (node (ref "XP2") (pin "13") (pinfunction "13_13") (pintype "passive"))
    )
    (net (code "4") (name "/IDC") (class "Default")
      (node (ref "C29") (pin "1") (pinfunction "1_1") (pintype "power_in"))
      (node (ref "R25") (pin "2") (pinfunction "2_2") (pintype "passive"))
      (node (ref "XP2") (pin "18") (pinfunction "18_18") (pintype "passive"))
    )
    (net (code "5") (name "/PGND_") (class "Default")
      (node (ref "C10") (pin "1") (pinfunction "1_1") (pintype "power_in"))
      (node (ref "C19") (pin "1") (pinfunction "1_1") (pintype "power_in"))
      (node (ref "C21") (pin "1") (pinfunction "1_1") (pintype "power_in"))
      (node (ref "C36") (pin "1") (pinfunction "1_1") (pintype "power_in"))
      (node (ref "C38") (pin "1") (pinfunction "1_1") (pintype "power_in"))
      (node (ref "C8") (pin "1") (pinfunction "1_1") (pintype "power_in"))
      (node (ref "DD1") (pin "16") (pinfunction "GNDL_16") (pintype "passive"))
      (node (ref "DD2") (pin "16") (pinfunction "GNDL_16") (pintype "passive"))
      (node (ref "DD3") (pin "16") (pinfunction "GNDL_16") (pintype "passive"))
      (node (ref "R21") (pin "1") (pinfunction "1_1") (pintype "passive"))
      (node (ref "R26") (pin "1") (pinfunction "1_1") (pintype "passive"))
      (node (ref "R27") (pin "1") (pinfunction "1_1") (pintype "passive"))
      (node (ref "R30") (pin "1") (pinfunction "1_1") (pintype "passive"))
      (node (ref "R37") (pin "1") (pinfunction "1_1") (pintype "passive"))
      (node (ref "R9") (pin "1") (pinfunction "1_1") (pintype "passive"))
      (node (ref "VD10") (pin "3") (pinfunction "A_3") (pintype "passive"))
      (node (ref "VD14") (pin "3") (pinfunction "A_3") (pintype "passive"))
      (node (ref "VD4") (pin "3") (pinfunction "A_3") (pintype "passive"))
      (node (ref "VT2") (pin "2") (pinfunction "S_2") (pintype "passive"))
      (node (ref "VT4") (pin "2") (pinfunction "S_2") (pintype "passive"))
      (node (ref "VT6") (pin "2") (pinfunction "S_2") (pintype "passive"))
    )
    (net (code "6") (name "/PWM_U_HI") (class "Default")
      (node (ref "DD1") (pin "12") (pinfunction "HIN_12") (pintype "passive"))
      (node (ref "R2") (pin "1") (pinfunction "1_1") (pintype "passive"))
      (node (ref "XP2") (pin "5") (pinfunction "5_5") (pintype "passive"))
    )
    (net (code "7") (name "/PWM_U_LO") (class "Default")
      (node (ref "DD1") (pin "14") (pinfunction "LIN_14") (pintype "passive"))
      (node (ref "R3") (pin "1") (pinfunction "1_1") (pintype "passive"))
      (node (ref "XP2") (pin "6") (pinfunction "6_6") (pintype "passive"))
    )
    (net (code "8") (name "/PWM_V_HI") (class "Default")
      (node (ref "DD2") (pin "12") (pinfunction "HIN_12") (pintype "passive"))
      (node (ref "R11") (pin "1") (pinfunction "1_1") (pintype "passive"))
      (node (ref "XP2") (pin "3") (pinfunction "3_3") (pintype "passive"))
    )
    (net (code "9") (name "/PWM_V_LO") (class "Default")
      (node (ref "DD2") (pin "14") (pinfunction "LIN_14") (pintype "passive"))
      (node (ref "R12") (pin "1") (pinfunction "1_1") (pintype "passive"))
      (node (ref "XP2") (pin "4") (pinfunction "4_4") (pintype "passive"))
    )
    (net (code "10") (name "/PWM_W_HI") (class "Default")
      (node (ref "DD3") (pin "12") (pinfunction "HIN_12") (pintype "passive"))
      (node (ref "R32") (pin "1") (pinfunction "1_1") (pintype "passive"))
      (node (ref "XP2") (pin "1") (pinfunction "1_1") (pintype "passive"))
    )
    (net (code "11") (name "/PWM_W_LO") (class "Default")
      (node (ref "DD3") (pin "14") (pinfunction "LIN_14") (pintype "passive"))
      (node (ref "R33") (pin "1") (pinfunction "1_1") (pintype "passive"))
      (node (ref "XP2") (pin "2") (pinfunction "2_2") (pintype "passive"))
    )
    (net (code "12") (name "/SD") (class "Default")
      (node (ref "DD1") (pin "13") (pinfunction "SD_13") (pintype "passive"))
      (node (ref "DD2") (pin "13") (pinfunction "SD_13") (pintype "passive"))
      (node (ref "DD3") (pin "13") (pinfunction "SD_13") (pintype "passive"))
      (node (ref "R4") (pin "1") (pinfunction "1_1") (pintype "passive"))
      (node (ref "XP2") (pin "8") (pinfunction "8_8") (pintype "passive"))
    )
    (net (code "13") (name "/UDC") (class "Default")
      (node (ref "C22") (pin "1") (pinfunction "1_1") (pintype "power_in"))
      (node (ref "R17") (pin "2") (pinfunction "2_2") (pintype "passive"))
      (node (ref "XP2") (pin "16") (pinfunction "16_16") (pintype "passive"))
    )
    (net (code "14") (name "3V3A") (class "Default")
      (node (ref "C30") (pin "2") (pinfunction "2_2") (pintype "power_in"))
      (node (ref "DA1") (pin "14") (pinfunction "+Vcc_14") (pintype "power_in"))
      (node (ref "VD7") (pin "3") (pinfunction "K_3") (pintype "passive"))
      (node (ref "VD9") (pin "3") (pinfunction "K_3") (pintype "passive"))
      (node (ref "XP2") (pin "15") (pinfunction "15_15") (pintype "passive"))
    )
    (net (code "15") (name "5V") (class "Default")
      (node (ref "C13") (pin "1") (pinfunction "1_1") (pintype "power_in"))
      (node (ref "C14") (pin "2") (pinfunction "2_2") (pintype "power_in"))
      (node (ref "C23") (pin "2") (pinfunction "2_2") (pintype "power_in"))
      (node (ref "C24") (pin "1") (pinfunction "1_1") (pintype "power_in"))
      (node (ref "C39") (pin "1") (pinfunction "1_1") (pintype "power_in"))
      (node (ref "C40") (pin "2") (pinfunction "2_2") (pintype "power_in"))
      (node (ref "DD1") (pin "10") (pinfunction "Ucc_10") (pintype "passive"))
      (node (ref "DD1") (pin "9") (pinfunction "Ut_9") (pintype "passive"))
      (node (ref "DD2") (pin "10") (pinfunction "Ucc_10") (pintype "passive"))
      (node (ref "DD2") (pin "9") (pinfunction "Ut_9") (pintype "passive"))
      (node (ref "DD3") (pin "10") (pinfunction "Ucc_10") (pintype "passive"))
      (node (ref "DD3") (pin "9") (pinfunction "Ut_9") (pintype "passive"))
      (node (ref "XP2") (pin "10") (pinfunction "10_10") (pintype "passive"))
      (node (ref "XP2") (pin "12") (pinfunction "12_12") (pintype "passive"))
    )
    (net (code "16") (name "AGND") (class "Default")
      (node (ref "C22") (pin "2") (pinfunction "2_2") (pintype "power_in"))
      (node (ref "C25") (pin "2") (pinfunction "2_2") (pintype "power_in"))
      (node (ref "C26") (pin "2") (pinfunction "2_2") (pintype "power_in"))
      (node (ref "C29") (pin "2") (pinfunction "2_2") (pintype "power_in"))
      (node (ref "C30") (pin "1") (pinfunction "1_1") (pintype "power_in"))
      (node (ref "C31") (pin "2") (pinfunction "2_2") (pintype "power_in"))
      (node (ref "DA1") (pin "6") (pinfunction "-Vcc_6") (pintype "power_in"))
      (node (ref "R18") (pin "1") (pinfunction "1_1") (pintype "passive"))
      (node (ref "R19") (pin "1") (pinfunction "1_1") (pintype "passive"))
      (node (ref "R31") (pin "1") (pinfunction "1_1") (pintype "passive"))
      (node (ref "XP2") (pin "17") (pinfunction "17_17") (pintype "passive"))
      (node (ref "XP4") (pin "1") (pinfunction "1_1") (pintype "passive"))
    )
    (net (code "17") (name "GND") (class "Default")
      (node (ref "C13") (pin "2") (pinfunction "2_2") (pintype "power_in"))
      (node (ref "C14") (pin "1") (pinfunction "1_1") (pintype "power_in"))
      (node (ref "C23") (pin "1") (pinfunction "1_1") (pintype "power_in"))
      (node (ref "C24") (pin "2") (pinfunction "2_2") (pintype "power_in"))
      (node (ref "C39") (pin "2") (pinfunction "2_2") (pintype "power_in"))
      (node (ref "C40") (pin "1") (pinfunction "1_1") (pintype "power_in"))
      (node (ref "DD1") (pin "11") (pinfunction "TIN_11") (pintype "passive"))
      (node (ref "DD1") (pin "15") (pinfunction "GND_15") (pintype "passive"))
      (node (ref "DD2") (pin "11") (pinfunction "TIN_11") (pintype "passive"))
      (node (ref "DD2") (pin "15") (pinfunction "GND_15") (pintype "passive"))
      (node (ref "DD3") (pin "11") (pinfunction "TIN_11") (pintype "passive"))
      (node (ref "DD3") (pin "15") (pinfunction "GND_15") (pintype "passive"))
      (node (ref "R11") (pin "2") (pinfunction "2_2") (pintype "passive"))
      (node (ref "R12") (pin "2") (pinfunction "2_2") (pintype "passive"))
      (node (ref "R2") (pin "2") (pinfunction "2_2") (pintype "passive"))
      (node (ref "R3") (pin "2") (pinfunction "2_2") (pintype "passive"))
      (node (ref "R32") (pin "2") (pinfunction "2_2") (pintype "passive"))
      (node (ref "R33") (pin "2") (pinfunction "2_2") (pintype "passive"))
      (node (ref "R4") (pin "2") (pinfunction "2_2") (pintype "passive"))
      (node (ref "XP2") (pin "7") (pinfunction "7_7") (pintype "passive"))
      (node (ref "XP2") (pin "9") (pinfunction "9_9") (pintype "passive"))
      (node (ref "XP3") (pin "1") (pinfunction "1_1") (pintype "passive"))
    )
    (net (code "18") (name "Net-(C28-Pad1)") (class "Default")
      (node (ref "C28") (pin "1") (pinfunction "1_1") (pintype "power_in"))
      (node (ref "R23") (pin "2") (pinfunction "2_2") (pintype "passive"))
      (node (ref "R24") (pin "1") (pinfunction "1_1") (pintype "passive"))
    )
    (net (code "19") (name "Net-(C28-Pad2)") (class "Default")
      (node (ref "C28") (pin "2") (pinfunction "2_2") (pintype "power_in"))
      (node (ref "R28") (pin "1") (pinfunction "1_1") (pintype "passive"))
      (node (ref "R30") (pin "2") (pinfunction "2_2") (pintype "passive"))
    )
    (net (code "20") (name "Net-(DA1A-+IN1)") (class "Default")
      (node (ref "C31") (pin "1") (pinfunction "1_1") (pintype "power_in"))
      (node (ref "DA1") (pin "5") (pinfunction "+IN1_5") (pintype "passive"))
      (node (ref "R28") (pin "2") (pinfunction "2_2") (pintype "passive"))
      (node (ref "R31") (pin "2") (pinfunction "2_2") (pintype "passive"))
    )
    (net (code "21") (name "Net-(DA1A--IN1)") (class "Default")
      (node (ref "C27") (pin "2") (pinfunction "2_2") (pintype "power_in"))
      (node (ref "DA1") (pin "4") (pinfunction "-IN1_4") (pintype "passive"))
      (node (ref "R22") (pin "1") (pinfunction "1_1") (pintype "passive"))
      (node (ref "R24") (pin "2") (pinfunction "2_2") (pintype "passive"))
    )
    (net (code "22") (name "Net-(DA1A-OUT1)") (class "Default")
      (node (ref "C27") (pin "1") (pinfunction "1_1") (pintype "power_in"))
      (node (ref "DA1") (pin "3") (pinfunction "OUT1_3") (pintype "passive"))
      (node (ref "R22") (pin "2") (pinfunction "2_2") (pintype "passive"))
      (node (ref "R25") (pin "1") (pinfunction "1_1") (pintype "passive"))
    )
    (net (code "23") (name "Net-(DA1B-+IN2)") (class "Default")
      (node (ref "C26") (pin "1") (pinfunction "1_1") (pintype "power_in"))
      (node (ref "DA1") (pin "11") (pinfunction "+IN2_11") (pintype "passive"))
      (node (ref "R16") (pin "1") (pinfunction "1_1") (pintype "passive"))
      (node (ref "R19") (pin "2") (pinfunction "2_2") (pintype "passive"))
      (node (ref "VD9") (pin "1") (pinfunction "A_1") (pintype "passive"))
    )
    (net (code "24") (name "Net-(DA1B--IN2)") (class "Default")
      (node (ref "DA1") (pin "12") (pinfunction "-IN2_12") (pintype "passive"))
      (node (ref "DA1") (pin "13") (pinfunction "OUT2_13") (pintype "passive"))
      (node (ref "R17") (pin "1") (pinfunction "1_1") (pintype "passive"))
    )
    (net (code "25") (name "Net-(DD1-OutH)") (class "Default")
      (node (ref "DD1") (pin "5") (pinfunction "OutH_5") (pintype "passive"))
      (node (ref "R5") (pin "1") (pinfunction "1_1") (pintype "passive"))
      (node (ref "VD15") (pin "3") (pinfunction "K_3") (pintype "passive"))
    )
    (net (code "26") (name "Net-(DD1-OutL)") (class "Default")
      (node (ref "DD1") (pin "1") (pinfunction "OutL_1") (pintype "passive"))
      (node (ref "R8") (pin "1") (pinfunction "1_1") (pintype "passive"))
      (node (ref "VD16") (pin "3") (pinfunction "K_3") (pintype "passive"))
    )
    (net (code "27") (name "Net-(DD1-UaH)") (class "Default")
      (node (ref "C4") (pin "2") (pinfunction "2_2") (pintype "power_in"))
      (node (ref "C6") (pin "2") (pinfunction "2_2") (pintype "power_in"))
      (node (ref "DD1") (pin "4") (pinfunction "UaH_4") (pintype "passive"))
      (node (ref "VD1") (pin "3") (pinfunction "K_3") (pintype "passive"))
    )
    (net (code "28") (name "Net-(DD2-OutH)") (class "Default")
      (node (ref "DD2") (pin "5") (pinfunction "OutH_5") (pintype "passive"))
      (node (ref "R13") (pin "1") (pinfunction "1_1") (pintype "passive"))
      (node (ref "VD17") (pin "3") (pinfunction "K_3") (pintype "passive"))
    )
    (net (code "29") (name "Net-(DD2-OutL)") (class "Default")
      (node (ref "DD2") (pin "1") (pinfunction "OutL_1") (pintype "passive"))
      (node (ref "R20") (pin "1") (pinfunction "1_1") (pintype "passive"))
      (node (ref "VD18") (pin "3") (pinfunction "K_3") (pintype "passive"))
    )
    (net (code "30") (name "Net-(DD2-UaH)") (class "Default")
      (node (ref "C15") (pin "2") (pinfunction "2_2") (pintype "power_in"))
      (node (ref "C17") (pin "2") (pinfunction "2_2") (pintype "power_in"))
      (node (ref "DD2") (pin "4") (pinfunction "UaH_4") (pintype "passive"))
      (node (ref "VD5") (pin "3") (pinfunction "K_3") (pintype "passive"))
    )
    (net (code "31") (name "Net-(DD3-OutH)") (class "Default")
      (node (ref "DD3") (pin "5") (pinfunction "OutH_5") (pintype "passive"))
      (node (ref "R34") (pin "1") (pinfunction "1_1") (pintype "passive"))
      (node (ref "VD19") (pin "3") (pinfunction "K_3") (pintype "passive"))
    )
    (net (code "32") (name "Net-(DD3-OutL)") (class "Default")
      (node (ref "DD3") (pin "1") (pinfunction "OutL_1") (pintype "passive"))
      (node (ref "R36") (pin "1") (pinfunction "1_1") (pintype "passive"))
      (node (ref "VD20") (pin "3") (pinfunction "K_3") (pintype "passive"))
    )
    (net (code "33") (name "Net-(DD3-UaH)") (class "Default")
      (node (ref "C32") (pin "2") (pinfunction "2_2") (pintype "power_in"))
      (node (ref "C34") (pin "2") (pinfunction "2_2") (pintype "power_in"))
      (node (ref "DD3") (pin "4") (pinfunction "UaH_4") (pintype "passive"))
      (node (ref "VD11") (pin "3") (pinfunction "K_3") (pintype "passive"))
    )
    (net (code "34") (name "Net-(VD1-A)") (class "Default")
      (node (ref "R1") (pin "2") (pinfunction "2_2") (pintype "passive"))
      (node (ref "VD1") (pin "1") (pinfunction "A_1") (pintype "passive"))
    )
    (net (code "35") (name "Net-(VD5-A)") (class "Default")
      (node (ref "R10") (pin "2") (pinfunction "2_2") (pintype "passive"))
      (node (ref "VD5") (pin "1") (pinfunction "A_1") (pintype "passive"))
    )
    (net (code "36") (name "Net-(VD10-K1)") (class "Default")
      (node (ref "R20") (pin "2") (pinfunction "2_2") (pintype "passive"))
      (node (ref "R21") (pin "2") (pinfunction "2_2") (pintype "passive"))
      (node (ref "VD10") (pin "1") (pinfunction "K1_1") (pintype "passive"))
      (node (ref "VD10") (pin "2") (pinfunction "K2_2") (pintype "passive"))
      (node (ref "VD18") (pin "1") (pinfunction "A_1") (pintype "passive"))
      (node (ref "VT4") (pin "1") (pinfunction "G_1") (pintype "passive"))
    )
    (net (code "37") (name "Net-(VD11-A)") (class "Default")
      (node (ref "R29") (pin "2") (pinfunction "2_2") (pintype "passive"))
      (node (ref "VD11") (pin "1") (pinfunction "A_1") (pintype "passive"))
    )
    (net (code "38") (name "Net-(VD13-K1)") (class "Default")
      (node (ref "R34") (pin "2") (pinfunction "2_2") (pintype "passive"))
      (node (ref "R35") (pin "2") (pinfunction "2_2") (pintype "passive"))
      (node (ref "VD13") (pin "1") (pinfunction "K1_1") (pintype "passive"))
      (node (ref "VD13") (pin "2") (pinfunction "K2_2") (pintype "passive"))
      (node (ref "VD19") (pin "1") (pinfunction "A_1") (pintype "passive"))
      (node (ref "VT5") (pin "1") (pinfunction "G_1") (pintype "passive"))
    )
    (net (code "39") (name "Net-(VD14-K1)") (class "Default")
      (node (ref "R36") (pin "2") (pinfunction "2_2") (pintype "passive"))
      (node (ref "R37") (pin "2") (pinfunction "2_2") (pintype "passive"))
      (node (ref "VD14") (pin "1") (pinfunction "K1_1") (pintype "passive"))
      (node (ref "VD14") (pin "2") (pinfunction "K2_2") (pintype "passive"))
      (node (ref "VD20") (pin "1") (pinfunction "A_1") (pintype "passive"))
      (node (ref "VT6") (pin "1") (pinfunction "G_1") (pintype "passive"))
    )
    (net (code "40") (name "Net-(VD15-A)") (class "Default")
      (node (ref "R5") (pin "2") (pinfunction "2_2") (pintype "passive"))
      (node (ref "R6") (pin "2") (pinfunction "2_2") (pintype "passive"))
      (node (ref "VD15") (pin "1") (pinfunction "A_1") (pintype "passive"))
      (node (ref "VD3") (pin "1") (pinfunction "K1_1") (pintype "passive"))
      (node (ref "VD3") (pin "2") (pinfunction "K2_2") (pintype "passive"))
      (node (ref "VT1") (pin "1") (pinfunction "G_1") (pintype "passive"))
    )
    (net (code "41") (name "Net-(VD16-A)") (class "Default")
      (node (ref "R8") (pin "2") (pinfunction "2_2") (pintype "passive"))
      (node (ref "R9") (pin "2") (pinfunction "2_2") (pintype "passive"))
      (node (ref "VD16") (pin "1") (pinfunction "A_1") (pintype "passive"))
      (node (ref "VD4") (pin "1") (pinfunction "K1_1") (pintype "passive"))
      (node (ref "VD4") (pin "2") (pinfunction "K2_2") (pintype "passive"))
      (node (ref "VT2") (pin "1") (pinfunction "G_1") (pintype "passive"))
    )
    (net (code "42") (name "Net-(VD17-A)") (class "Default")
      (node (ref "R13") (pin "2") (pinfunction "2_2") (pintype "passive"))
      (node (ref "R14") (pin "2") (pinfunction "2_2") (pintype "passive"))
      (node (ref "VD17") (pin "1") (pinfunction "A_1") (pintype "passive"))
      (node (ref "VD8") (pin "1") (pinfunction "K1_1") (pintype "passive"))
      (node (ref "VD8") (pin "2") (pinfunction "K2_2") (pintype "passive"))
      (node (ref "VT3") (pin "1") (pinfunction "G_1") (pintype "passive"))
    )
    (net (code "43") (name "Net-(VD21-C)") (class "Default")
      (node (ref "R38") (pin "2") (pinfunction "2_2") (pintype "passive"))
      (node (ref "VD21") (pin "2") (pinfunction "C_2") (pintype "passive"))
    )
    (net (code "44") (name "PGND") (class "Default")
      (node (ref "C1") (pin "2") (pinfunction "2_2") (pintype "power_in"))
      (node (ref "C11") (pin "2") (pinfunction "2_2") (pintype "power_in"))
      (node (ref "C12") (pin "2") (pinfunction "2_2") (pintype "power_in"))
      (node (ref "C18") (pin "2") (pinfunction "2_2") (pintype "power_in"))
      (node (ref "C2") (pin "2") (pinfunction "2_2") (pintype "power_in"))
      (node (ref "C3") (pin "2") (pinfunction "2_2") (pintype "power_in"))
      (node (ref "C35") (pin "2") (pinfunction "2_2") (pintype "power_in"))
      (node (ref "C7") (pin "2") (pinfunction "2_2") (pintype "power_in"))
      (node (ref "R23") (pin "1") (pinfunction "1_1") (pintype "passive"))
      (node (ref "R26") (pin "2") (pinfunction "2_2") (pintype "passive"))
      (node (ref "R27") (pin "2") (pinfunction "2_2") (pintype "passive"))
      (node (ref "R38") (pin "1") (pinfunction "1_1") (pintype "passive"))
      (node (ref "R7") (pin "1") (pinfunction "1_1") (pintype "passive"))
      (node (ref "VD12") (pin "1") (pinfunction "A_1") (pintype "passive"))
      (node (ref "VD2") (pin "1") (pinfunction "A_1") (pintype "passive"))
      (node (ref "VD6") (pin "1") (pinfunction "A_1") (pintype "passive"))
      (node (ref "XP1") (pin "2") (pinfunction "2_2") (pintype "passive"))
      (node (ref "XP1") (pin "5") (pinfunction "5_5") (pintype "passive"))
      (node (ref "XP1") (pin "6") (pinfunction "6_6") (pintype "passive"))
      (node (ref "XP5") (pin "1") (pinfunction "1_1") (pintype "passive"))
    )
    (net (code "45") (name "U") (class "Default")
      (node (ref "C4") (pin "1") (pinfunction "1_1") (pintype "power_in"))
      (node (ref "C6") (pin "1") (pinfunction "1_1") (pintype "power_in"))
      (node (ref "DD1") (pin "6") (pinfunction "GNDH_6") (pintype "passive"))
      (node (ref "R6") (pin "1") (pinfunction "1_1") (pintype "passive"))
      (node (ref "VD3") (pin "3") (pinfunction "A_3") (pintype "passive"))
      (node (ref "VT1") (pin "2") (pinfunction "S_2") (pintype "passive"))
      (node (ref "VT2") (pin "3") (pinfunction "D_3") (pintype "passive"))
      (node (ref "XT1") (pin "1") (pinfunction "1_1") (pintype "power_in"))
    )
    (net (code "46") (name "V") (class "Default")
      (node (ref "C15") (pin "1") (pinfunction "1_1") (pintype "power_in"))
      (node (ref "C17") (pin "1") (pinfunction "1_1") (pintype "power_in"))
      (node (ref "DD2") (pin "6") (pinfunction "GNDH_6") (pintype "passive"))
      (node (ref "R14") (pin "1") (pinfunction "1_1") (pintype "passive"))
      (node (ref "VD8") (pin "3") (pinfunction "A_3") (pintype "passive"))
      (node (ref "VT3") (pin "2") (pinfunction "S_2") (pintype "passive"))
      (node (ref "VT4") (pin "3") (pinfunction "D_3") (pintype "passive"))
      (node (ref "XT1") (pin "2") (pinfunction "2_2") (pintype "power_in"))
    )
    (net (code "47") (name "W") (class "Default")
      (node (ref "C32") (pin "1") (pinfunction "1_1") (pintype "power_in"))
      (node (ref "C34") (pin "1") (pinfunction "1_1") (pintype "power_in"))
      (node (ref "DD3") (pin "6") (pinfunction "GNDH_6") (pintype "passive"))
      (node (ref "R35") (pin "1") (pinfunction "1_1") (pintype "passive"))
      (node (ref "VD13") (pin "3") (pinfunction "A_3") (pintype "passive"))
      (node (ref "VT5") (pin "2") (pinfunction "S_2") (pintype "passive"))
      (node (ref "VT6") (pin "3") (pinfunction "D_3") (pintype "passive"))
      (node (ref "XT1") (pin "3") (pinfunction "3_3") (pintype "power_in"))
    )
    (net (code "48") (name "unconnected-(DA1A-NC-Pad1)") (class "Default")
      (node (ref "DA1") (pin "1") (pinfunction "NC_1") (pintype "passive"))
    )
    (net (code "49") (name "unconnected-(DA1A-NC-Pad2)") (class "Default")
      (node (ref "DA1") (pin "2") (pinfunction "NC_2") (pintype "passive"))
    )
    (net (code "50") (name "unconnected-(DA1A-NC-Pad7)") (class "Default")
      (node (ref "DA1") (pin "7") (pinfunction "NC_7") (pintype "passive"))
    )
    (net (code "51") (name "unconnected-(DA1A-NC-Pad8)") (class "Default")
      (node (ref "DA1") (pin "8") (pinfunction "NC_8") (pintype "passive"))
    )
    (net (code "52") (name "unconnected-(DA1A-NC-Pad9)") (class "Default")
      (node (ref "DA1") (pin "9") (pinfunction "NC_9") (pintype "passive"))
    )
    (net (code "53") (name "unconnected-(DA1A-NC-Pad10)") (class "Default")
      (node (ref "DA1") (pin "10") (pinfunction "NC_10") (pintype "passive"))
    )
    (net (code "54") (name "unconnected-(DA1A-NC-Pad15)") (class "Default")
      (node (ref "DA1") (pin "15") (pinfunction "NC_15") (pintype "passive"))
    )
    (net (code "55") (name "unconnected-(DA1A-NC-Pad16)") (class "Default")
      (node (ref "DA1") (pin "16") (pinfunction "NC_16") (pintype "passive"))
    )
    (net (code "56") (name "unconnected-(XP2-Pad11)") (class "Default")
      (node (ref "XP2") (pin "11") (pinfunction "11_11") (pintype "passive+no_connect"))
    )
    (net (code "57") (name "unconnected-(XP2-Pad14)") (class "Default")
      (node (ref "XP2") (pin "14") (pinfunction "14_14") (pintype "passive+no_connect"))
    )
  )
)
